# 16_-CLOCK.net
KiCad netlist of a schematic drawn in Altium Designer
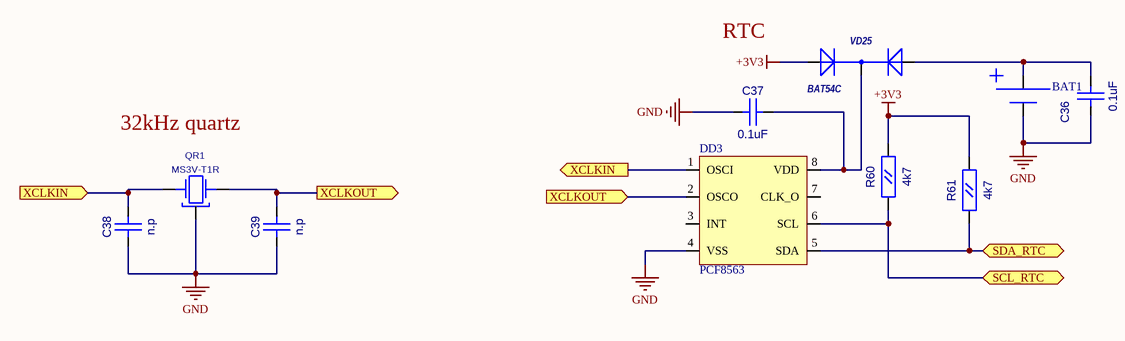
[diagram p0: [16]-CLOCK.SchDoc]

(export (version "E")
  (design (tool "Eeschema 10.0.6"))
  (components
    (comp (ref "BAT1")
      (value "CR2032-VBY4")
      (footprint "CR2032_ONBOARD")
      (libsource (lib "fizik_lib") (part "CR2032-VBY2"))
    )
    (comp (ref "C36")
      (value "0.1uF")
      (footprint "CC0603")
      (description "CC0603")
      (libsource (lib "gprs_modem_2") (part "CC0603"))
    )
    (comp (ref "C37")
      (value "0.1uF")
      (footprint "CC0603")
      (description "CC0603")
      (libsource (lib "gprs_modem_2") (part "CC0603"))
    )
    (comp (ref "C38")
      (value "n.p")
      (footprint "CC0603")
      (description "CC0603")
      (libsource (lib "gprs_modem_2") (part "CC0603"))
    )
    (comp (ref "C39")
      (value "n.p")
      (footprint "CC0603")
      (description "CC0603")
      (libsource (lib "gprs_modem_2") (part "CC0603"))
    )
    (comp (ref "DD3") (value "PCF8563") (footprint "SO-8") (libsource (lib "gprs_modem") (part "PCF8563")))
    (comp (ref "QR1")
      (value "MS3V-T1R")
      (footprint "MS3V-T1R")
      (description "CRYSTAL_32768 Hz")
      (libsource (lib "gprs_modem") (part "MS3V-T1R"))
    )
    (comp (ref "R60")
      (value "4k7")
      (footprint "RC0603")
      (description "RC0603")
      (libsource (lib "gprs_modem_2") (part "RC0603"))
    )
    (comp (ref "R61")
      (value "4k7")
      (footprint "RC0603")
      (description "RC0603")
      (libsource (lib "gprs_modem_2") (part "RC0603"))
    )
    (comp (ref "VD25")
      (value "BAT54C")
      (footprint "SOT-23(123)")
      (libsource (lib "gprs_modem_2") (part "BAT54C"))
    )
  )
  (nets
    (net (code "1") (name "+3V3") (class "Default")
      (node (ref "R60") (pin "2") (pinfunction "B_2") (pintype "passive"))
      (node (ref "R61") (pin "2") (pinfunction "B_2") (pintype "passive"))
      (node (ref "VD25") (pin "1") (pinfunction "A_1") (pintype "passive"))
    )
    (net (code "2") (name "/SCL_RTC") (class "Default")
      (node (ref "DD3") (pin "6") (pinfunction "SCL_6") (pintype "passive"))
      (node (ref "R60") (pin "1") (pinfunction "A_1") (pintype "passive"))
    )
    (net (code "3") (name "/SDA_RTC") (class "Default")
      (node (ref "DD3") (pin "5") (pinfunction "SDA_5") (pintype "passive"))
      (node (ref "R61") (pin "1") (pinfunction "A_1") (pintype "passive"))
    )
    (net (code "4") (name "/XCLKIN") (class "Default")
      (node (ref "C38") (pin "2") (pinfunction "B_2") (pintype "passive"))
      (node (ref "DD3") (pin "1") (pinfunction "OSCI_1") (pintype "passive"))
      (node (ref "QR1") (pin "2") (pinfunction "X2_2") (pintype "passive"))
    )
    (net (code "5") (name "/XCLKOUT") (class "Default")
      (node (ref "C39") (pin "2") (pinfunction "B_2") (pintype "passive"))
      (node (ref "DD3") (pin "2") (pinfunction "OSCO_2") (pintype "passive"))
      (node (ref "QR1") (pin "1") (pinfunction "X1_1") (pintype "passive"))
    )
    (net (code "6") (name "GND") (class "Default")
      (node (ref "BAT1") (pin "1") (pintype "passive"))
      (node (ref "C36") (pin "1") (pinfunction "A_1") (pintype "passive"))
      (node (ref "C37") (pin "1") (pinfunction "A_1") (pintype "passive"))
      (node (ref "C38") (pin "1") (pinfunction "A_1") (pintype "passive"))
      (node (ref "C39") (pin "1") (pinfunction "A_1") (pintype "passive"))
      (node (ref "DD3") (pin "4") (pinfunction "VSS_4") (pintype "passive"))
      (node (ref "QR1") (pin "3") (pinfunction "3_3") (pintype "passive"))
    )
    (net (code "7") (name "Net-(C36-B)") (class "Default")
      (node (ref "BAT1") (pin "2") (pintype "passive"))
      (node (ref "C36") (pin "2") (pinfunction "B_2") (pintype "passive"))
      (node (ref "VD25") (pin "2") (pinfunction "A_2") (pintype "passive"))
    )
    (net (code "8") (name "Net-(C37-B)") (class "Default")
      (node (ref "C37") (pin "2") (pinfunction "B_2") (pintype "passive"))
      (node (ref "DD3") (pin "8") (pinfunction "VDD_8") (pintype "passive"))
      (node (ref "VD25") (pin "3") (pinfunction "K_3") (pintype "passive"))
    )
    (net (code "9") (name "unconnected-(DD3-CLK_O-Pad7)") (class "Default")
      (node (ref "DD3") (pin "7") (pinfunction "CLK_O_7") (pintype "passive"))
    )
    (net (code "10") (name "unconnected-(DD3-INT-Pad3)") (class "Default")
      (node (ref "DD3") (pin "3") (pinfunction "INT_3") (pintype "passive"))
    )
  )
)
